# Interfaces.net
KiCad netlist of a schematic drawn in Altium Designer
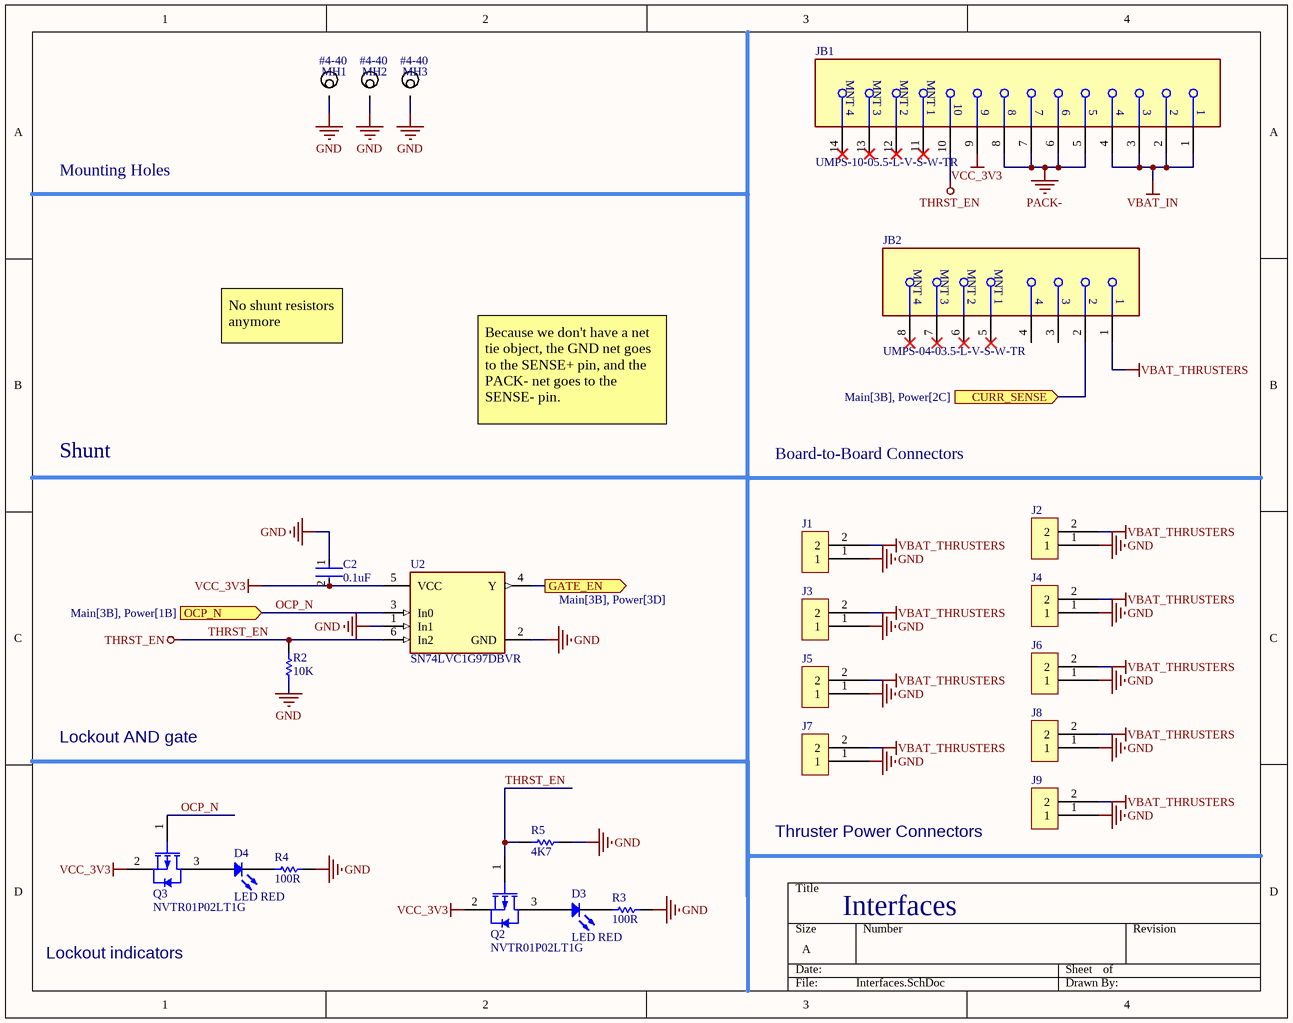
[diagram p0: Interfaces.SchDoc]

(export (version "E")
  (design (tool "Eeschema 10.0.6"))
  (components
    (comp (ref "C2")
      (value "0.1uF")
      (footprint "FP-C0603C-CF-MFG")
      (description "CAP CER 0.1UF 10V X7R 0603")
      (fields (field (name "TOLERANCE") "0.1") (field (name "MANUFACTURER PART NUMBER") "C0603C104K8RACTU"))
      (libsource (lib "Altium Content Vault") (part "b4654b650e69147ec39a6b967a45e02"))
    )
    (comp (ref "D3")
      (value "LED RED")
      (footprint "C0805")
      (description "led\r\n LTST-C171KRKT")
      (fields
        (field (name "MANUFACTURER") "Lite-On Inc.")
        (field (name "MANUFACTURER PART NUMBER") "LTST-C171KRKT")
      )
      (libsource (lib "CMR_Miscellaneous_Devices") (part "LED0"))
    )
    (comp (ref "D4")
      (value "LED RED")
      (footprint "C0805")
      (description "led\r\n LTST-C171KRKT")
      (fields
        (field (name "MANUFACTURER") "Lite-On Inc.")
        (field (name "MANUFACTURER PART NUMBER") "LTST-C171KRKT")
      )
      (libsource (lib "CMR_Miscellaneous_Devices") (part "LED0"))
    )
    (comp (ref "J1")
      (value "~")
      (footprint "2-pin Megafit RA")
      (libsource (lib "TAUV-Lib") (part "2-pin megafit"))
    )
    (comp (ref "J2")
      (value "~")
      (footprint "2-pin Megafit RA")
      (libsource (lib "TAUV-Lib") (part "2-pin megafit"))
    )
    (comp (ref "J3")
      (value "~")
      (footprint "2-pin Megafit RA")
      (libsource (lib "TAUV-Lib") (part "2-pin megafit"))
    )
    (comp (ref "J4")
      (value "~")
      (footprint "2-pin Megafit RA")
      (libsource (lib "TAUV-Lib") (part "2-pin megafit"))
    )
    (comp (ref "J5")
      (value "~")
      (footprint "2-pin Megafit RA")
      (libsource (lib "TAUV-Lib") (part "2-pin megafit"))
    )
    (comp (ref "J6")
      (value "~")
      (footprint "2-pin Megafit RA")
      (libsource (lib "TAUV-Lib") (part "2-pin megafit"))
    )
    (comp (ref "J7")
      (value "~")
      (footprint "2-pin Megafit RA")
      (libsource (lib "TAUV-Lib") (part "2-pin megafit"))
    )
    (comp (ref "J8")
      (value "~")
      (footprint "2-pin Megafit RA")
      (libsource (lib "TAUV-Lib") (part "2-pin megafit"))
    )
    (comp (ref "J9")
      (value "~")
      (footprint "2-pin Megafit RA")
      (libsource (lib "Tauv-Lib") (part "2-pin megafit"))
    )
    (comp (ref "JB1")
      (value "UMPS-10-05.5-L-V-S-W-TR")
      (footprint "FP-UMPS-10-05_5-L-V-S-W-T-MFG")
      (description "CONN MPOWER 2MM FMALE 10POS GOLD")
      (libsource (lib "Altium Content Vault") (part "50ca1e906762132617f05a77d1e0c4c"))
    )
    (comp (ref "JB2")
      (value "UMPS-04-03.5-L-V-S-W-TR")
      (footprint "FP-UMPS-04-03_5-L-V-S-W-T-MFG")
      (description "CONN MPOWER 2MM FMALE 4POS GOLD")
      (libsource (lib "Altium Content Vault") (part "04dfb715127717a7ff8d0007f751750"))
    )
    (comp (ref "MH1")
      (value "#4-40")
      (footprint "Mounting Hole #4-40")
      (description "Mounting Hole for ANSI #4-40 w/ Flat Washer, Loose Fit")
      (libsource (lib "TAUV-Lib") (part "Mounting Hole #4-40, Loose Fit"))
    )
    (comp (ref "MH2")
      (value "#4-40")
      (footprint "Mounting Hole #4-40")
      (description "Mounting Hole for ANSI #4-40 w/ Flat Washer, Loose Fit")
      (libsource (lib "TAUV-Lib") (part "Mounting Hole #4-40, Loose Fit"))
    )
    (comp (ref "MH3")
      (value "#4-40")
      (footprint "Mounting Hole #4-40")
      (description "Mounting Hole for ANSI #4-40 w/ Flat Washer, Loose Fit")
      (libsource (lib "TAUV-Lib") (part "Mounting Hole #4-40, Loose Fit"))
    )
    (comp (ref "Q2")
      (value "NVTR01P02LT1G")
      (footprint "ONSC-SOT-23-3-318-08_V")
      (description "Power MOSFET, -20 V, -1.3 A, P-Channel, 3-Pin SOT-23, Pb-Free, Tape and Reel")
      (fields (field (name "MANUFACTURER") "On Semiconductor"))
      (libsource (lib "Altium Content Vault") (part "ONSC-PMOS-G1S2D3-3_D"))
    )
    (comp (ref "Q3")
      (value "NVTR01P02LT1G")
      (footprint "ONSC-SOT-23-3-318-08_V")
      (description "Power MOSFET, -20 V, -1.3 A, P-Channel, 3-Pin SOT-23, Pb-Free, Tape and Reel")
      (fields (field (name "MANUFACTURER") "On Semiconductor"))
      (libsource (lib "Altium Content Vault") (part "ONSC-PMOS-G1S2D3-3_D"))
    )
    (comp (ref "R2")
      (value "10K")
      (footprint "RESC0603(1608)_N")
      (description "10K 0.1W 5% 0603 (1608 Metric)  SMD")
      (fields (field (name "TOLERANCE") "5 %") (field (name "POWER") "0.1 W"))
      (libsource (lib "Altium Content Vault") (part "RES"))
    )
    (comp (ref "R3")
      (value "100R")
      (footprint "RESC1609X50X30NL10T20")
      (description "100R 0.1W 5%")
      (fields (field (name "PART NUMBER") "CRCW0603100RJNTA") (field (name "MANUFACTURER") "Vishay Dale"))
      (libsource (lib "Altium Content Vault") (part "RES"))
    )
    (comp (ref "R4")
      (value "100R")
      (footprint "RESC1609X50X30NL10T20")
      (description "100R 0.1W 5%")
      (fields (field (name "PART NUMBER") "CRCW0603100RJNTA") (field (name "MANUFACTURER") "Vishay Dale"))
      (libsource (lib "Altium Content Vault") (part "RES"))
    )
    (comp (ref "R5")
      (value "4K7")
      (footprint "0603")
      (description "4K7 0.1W 1% 0603 (1608 Metric)  SMD")
      (fields (field (name "POWER") "0.1 W") (field (name "TOLERANCE") "1 %"))
      (libsource (lib "TAUV-Lib") (part "4K7 0603"))
    )
    (comp (ref "U2")
      (value "SN74LVC1G97DBVR")
      (footprint "FP-DBV0006A-MFG")
      (description "IC CONFIG MULT-FUNC GATE SOT23-6")
      (fields
        (field (name "OCTOPART") "https://octopart.com/sn74lvc1g97dbvr-texas+instruments-464842")
        (field (name "MANUFACTURER") "Texas Instruments")
      )
      (libsource (lib "Altium Content Vault") (part "a1876f62f2ab2790f28bb26e63f2887"))
    )
  )
  (nets
    (net (code "1") (name "/CURR_SENSE") (class "Default")
      (node (ref "JB2") (pin "2") (pinfunction "2_2") (pintype "passive"))
    )
    (net (code "2") (name "/GATE_EN") (class "Default")
      (node (ref "U2") (pin "4") (pinfunction "Y_4") (pintype "output"))
    )
    (net (code "3") (name "/OCP_N") (class "Default")
      (node (ref "Q3") (pin "1") (pinfunction "G_1") (pintype "passive"))
      (node (ref "U2") (pin "3") (pinfunction "In0_3") (pintype "input"))
    )
    (net (code "4") (name "GND") (class "Default")
      (node (ref "C2") (pin "1") (pinfunction "1_1") (pintype "passive"))
      (node (ref "J1") (pin "1") (pinfunction "1_1") (pintype "passive"))
      (node (ref "J2") (pin "1") (pinfunction "1_1") (pintype "passive"))
      (node (ref "J3") (pin "1") (pinfunction "1_1") (pintype "passive"))
      (node (ref "J4") (pin "1") (pinfunction "1_1") (pintype "passive"))
      (node (ref "J5") (pin "1") (pinfunction "1_1") (pintype "passive"))
      (node (ref "J6") (pin "1") (pinfunction "1_1") (pintype "passive"))
      (node (ref "J7") (pin "1") (pinfunction "1_1") (pintype "passive"))
      (node (ref "J8") (pin "1") (pinfunction "1_1") (pintype "passive"))
      (node (ref "J9") (pin "1") (pinfunction "1_1") (pintype "passive"))
      (node (ref "MH1") (pin "0") (pinfunction "0_0") (pintype "passive"))
      (node (ref "MH2") (pin "0") (pinfunction "0_0") (pintype "passive"))
      (node (ref "MH3") (pin "0") (pinfunction "0_0") (pintype "passive"))
      (node (ref "R2") (pin "2") (pinfunction "2_2") (pintype "passive"))
      (node (ref "R3") (pin "2") (pinfunction "2_2") (pintype "passive"))
      (node (ref "R4") (pin "2") (pinfunction "2_2") (pintype "passive"))
      (node (ref "R5") (pin "1") (pinfunction "1_1") (pintype "passive"))
      (node (ref "U2") (pin "1") (pinfunction "In1_1") (pintype "input"))
      (node (ref "U2") (pin "2") (pinfunction "GND_2") (pintype "power_in"))
    )
    (net (code "5") (name "Net-(D3-A)") (class "Default")
      (node (ref "D3") (pin "2") (pinfunction "A_2") (pintype "passive"))
      (node (ref "Q2") (pin "3") (pinfunction "D_3") (pintype "passive"))
    )
    (net (code "6") (name "Net-(D3-K)") (class "Default")
      (node (ref "D3") (pin "1") (pinfunction "K_1") (pintype "passive"))
      (node (ref "R3") (pin "1") (pinfunction "1_1") (pintype "passive"))
    )
    (net (code "7") (name "Net-(D4-A)") (class "Default")
      (node (ref "D4") (pin "2") (pinfunction "A_2") (pintype "passive"))
      (node (ref "Q3") (pin "3") (pinfunction "D_3") (pintype "passive"))
    )
    (net (code "8") (name "Net-(D4-K)") (class "Default")
      (node (ref "D4") (pin "1") (pinfunction "K_1") (pintype "passive"))
      (node (ref "R4") (pin "1") (pinfunction "1_1") (pintype "passive"))
    )
    (net (code "9") (name "PACK-") (class "Default")
      (node (ref "JB1") (pin "5") (pinfunction "5_5") (pintype "passive"))
      (node (ref "JB1") (pin "6") (pinfunction "6_6") (pintype "passive"))
      (node (ref "JB1") (pin "7") (pinfunction "7_7") (pintype "passive"))
      (node (ref "JB1") (pin "8") (pinfunction "8_8") (pintype "passive"))
    )
    (net (code "10") (name "THRST_EN") (class "Default")
      (node (ref "JB1") (pin "10") (pinfunction "10_10") (pintype "passive"))
      (node (ref "Q2") (pin "1") (pinfunction "G_1") (pintype "passive"))
      (node (ref "R2") (pin "1") (pinfunction "1_1") (pintype "passive"))
      (node (ref "R5") (pin "2") (pinfunction "2_2") (pintype "passive"))
      (node (ref "U2") (pin "6") (pinfunction "In2_6") (pintype "input"))
    )
    (net (code "11") (name "VBAT_IN") (class "Default")
      (node (ref "JB1") (pin "1") (pinfunction "1_1") (pintype "passive"))
      (node (ref "JB1") (pin "2") (pinfunction "2_2") (pintype "passive"))
      (node (ref "JB1") (pin "3") (pinfunction "3_3") (pintype "passive"))
      (node (ref "JB1") (pin "4") (pinfunction "4_4") (pintype "passive"))
    )
    (net (code "12") (name "VBAT_THRUSTERS") (class "Default")
      (node (ref "J1") (pin "2") (pinfunction "2_2") (pintype "passive"))
      (node (ref "J2") (pin "2") (pinfunction "2_2") (pintype "passive"))
      (node (ref "J3") (pin "2") (pinfunction "2_2") (pintype "passive"))
      (node (ref "J4") (pin "2") (pinfunction "2_2") (pintype "passive"))
      (node (ref "J5") (pin "2") (pinfunction "2_2") (pintype "passive"))
      (node (ref "J6") (pin "2") (pinfunction "2_2") (pintype "passive"))
      (node (ref "J7") (pin "2") (pinfunction "2_2") (pintype "passive"))
      (node (ref "J8") (pin "2") (pinfunction "2_2") (pintype "passive"))
      (node (ref "J9") (pin "2") (pinfunction "2_2") (pintype "passive"))
      (node (ref "JB2") (pin "1") (pinfunction "1_1") (pintype "passive"))
    )
    (net (code "13") (name "VCC_3V3") (class "Default")
      (node (ref "C2") (pin "2") (pinfunction "2_2") (pintype "passive"))
      (node (ref "JB1") (pin "9") (pinfunction "9_9") (pintype "passive"))
      (node (ref "Q2") (pin "2") (pinfunction "S_2") (pintype "passive"))
      (node (ref "Q3") (pin "2") (pinfunction "S_2") (pintype "passive"))
      (node (ref "U2") (pin "5") (pinfunction "VCC_5") (pintype "power_in"))
    )
    (net (code "14") (name "unconnected-(JB1-MNT_1-Pad11)") (class "Default")
      (node (ref "JB1") (pin "11") (pinfunction "MNT_1_11") (pintype "passive+no_connect"))
    )
    (net (code "15") (name "unconnected-(JB1-MNT_2-Pad12)") (class "Default")
      (node (ref "JB1") (pin "12") (pinfunction "MNT_2_12") (pintype "passive+no_connect"))
    )
    (net (code "16") (name "unconnected-(JB1-MNT_3-Pad13)") (class "Default")
      (node (ref "JB1") (pin "13") (pinfunction "MNT_3_13") (pintype "passive+no_connect"))
    )
    (net (code "17") (name "unconnected-(JB1-MNT_4-Pad14)") (class "Default")
      (node (ref "JB1") (pin "14") (pinfunction "MNT_4_14") (pintype "passive+no_connect"))
    )
    (net (code "18") (name "unconnected-(JB2-MNT_1-Pad5)") (class "Default")
      (node (ref "JB2") (pin "5") (pinfunction "MNT_1_5") (pintype "passive+no_connect"))
    )
    (net (code "19") (name "unconnected-(JB2-MNT_2-Pad6)") (class "Default")
      (node (ref "JB2") (pin "6") (pinfunction "MNT_2_6") (pintype "passive+no_connect"))
    )
    (net (code "20") (name "unconnected-(JB2-MNT_3-Pad7)") (class "Default")
      (node (ref "JB2") (pin "7") (pinfunction "MNT_3_7") (pintype "passive+no_connect"))
    )
    (net (code "21") (name "unconnected-(JB2-MNT_4-Pad8)") (class "Default")
      (node (ref "JB2") (pin "8") (pinfunction "MNT_4_8") (pintype "passive+no_connect"))
    )
    (net (code "22") (name "unconnected-(JB2-Pad3)") (class "Default")
      (node (ref "JB2") (pin "3") (pinfunction "3_3") (pintype "passive"))
    )
    (net (code "23") (name "unconnected-(JB2-Pad4)") (class "Default")
      (node (ref "JB2") (pin "4") (pinfunction "4_4") (pintype "passive"))
    )
  )
)
